# Power.net
KiCad netlist of a schematic drawn in Altium Designer
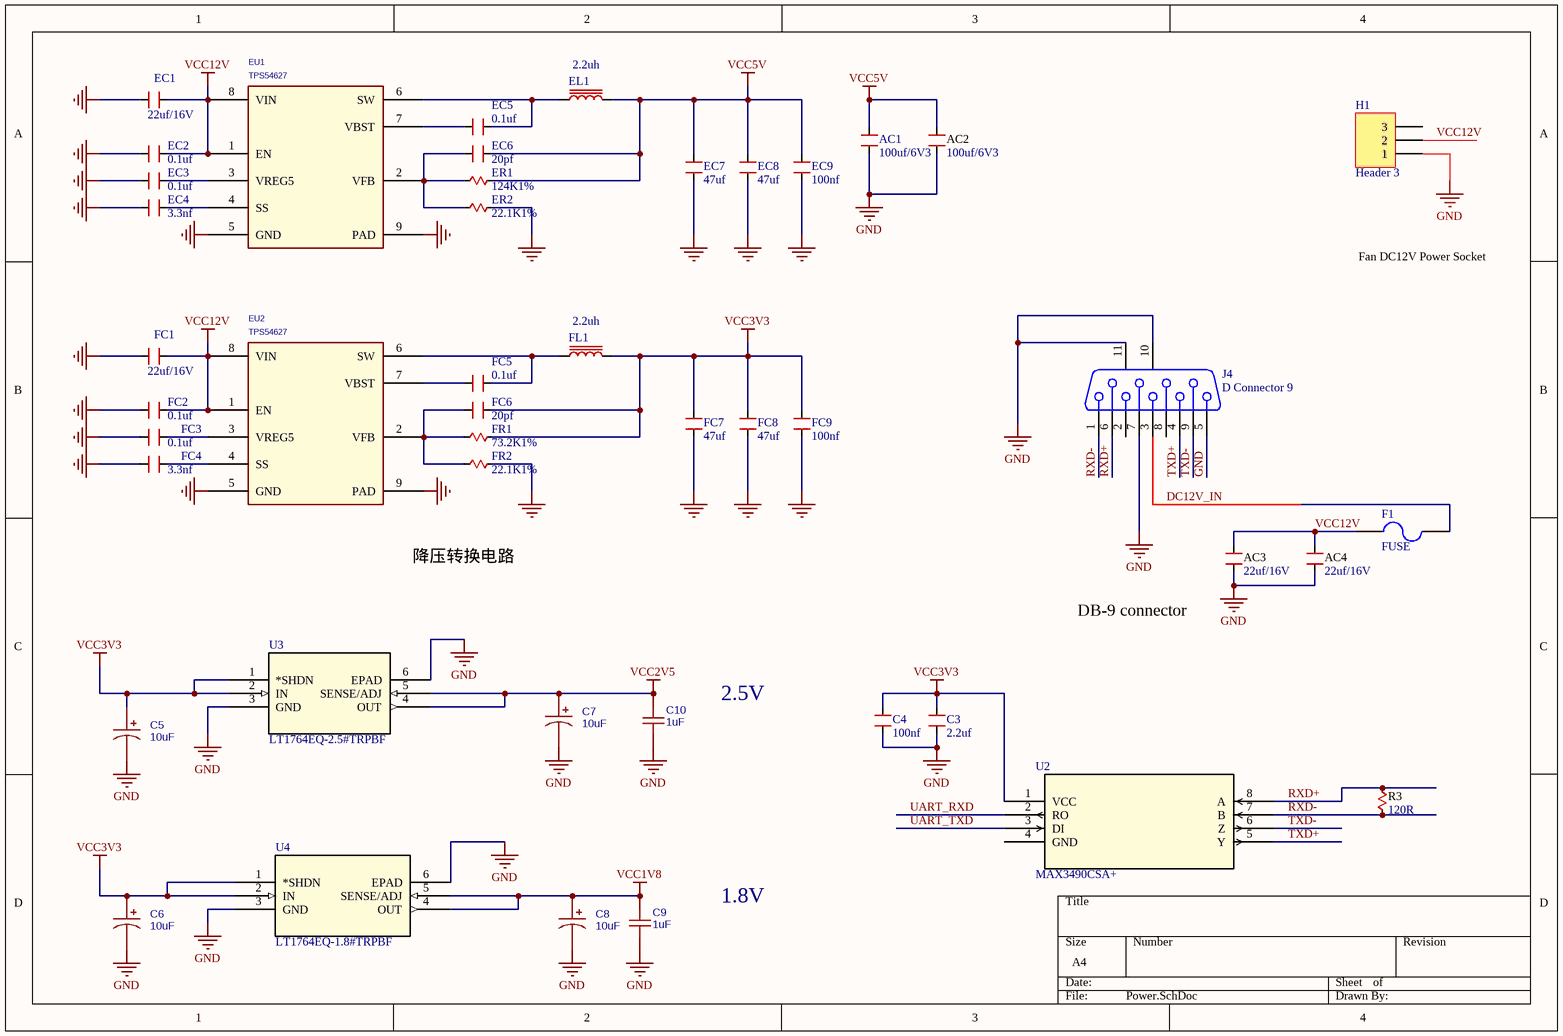
[diagram p0: Power.SchDoc]

(export (version "E")
  (design (tool "Eeschema 10.0.6"))
  (components
    (comp (ref "AC1")
      (value "100uf/6V3")
      (footprint "CAP1206")
      (description "Generic Capacitor")
      (libsource (lib "Miz702fun_20160501") (part "CAPACITOR"))
    )
    (comp (ref "AC2")
      (value "100uf/6V3")
      (footprint "CAP1206")
      (description "Generic Capacitor")
      (libsource (lib "MIZ7035_定制") (part "CAPACITOR"))
    )
    (comp (ref "AC3")
      (value "22uf/16V")
      (footprint "CAP1206")
      (description "Generic Capacitor")
      (libsource (lib "MIZ7035_定制") (part "CAPACITOR"))
    )
    (comp (ref "AC4")
      (value "22uf/16V")
      (footprint "CAP1206")
      (description "Generic Capacitor")
      (libsource (lib "MIZ7035_定制") (part "CAPACITOR"))
    )
    (comp (ref "C3")
      (value "2.2uf")
      (footprint "CAP0402")
      (description "Generic Capacitor")
      (libsource (lib "Miz702fun_20160501") (part "CAPACITOR"))
    )
    (comp (ref "C4")
      (value "100nf")
      (footprint "CAP0402")
      (description "Generic Capacitor")
      (libsource (lib "MainNewLib") (part "CAPACITOR_1"))
    )
    (comp (ref "C5")
      (value "10uF")
      (footprint "CASE-A_3216")
      (fields (field (name "CONTRIBUTOR") "LCEDA_Lib"))
      (libsource (lib "Sub-board") (part "150u"))
    )
    (comp (ref "C6")
      (value "10uF")
      (footprint "CASE-A_3216")
      (fields (field (name "CONTRIBUTOR") "LCEDA_Lib"))
      (libsource (lib "Sub-board") (part "150u"))
    )
    (comp (ref "C7")
      (value "10uF")
      (footprint "CASE-A_3216")
      (fields (field (name "CONTRIBUTOR") "LCEDA_Lib"))
      (libsource (lib "Sub-board") (part "150u"))
    )
    (comp (ref "C8")
      (value "10uF")
      (footprint "CASE-A_3216")
      (fields (field (name "CONTRIBUTOR") "LCEDA_Lib"))
      (libsource (lib "Sub-board") (part "150u"))
    )
    (comp (ref "C9")
      (value "1uF")
      (footprint "CAP0402")
      (fields (field (name "CONTRIBUTOR") "LCEDA_Lib"))
      (libsource (lib "Sub-board") (part "1u"))
    )
    (comp (ref "C10")
      (value "1uF")
      (footprint "CAP0402")
      (fields (field (name "CONTRIBUTOR") "LCEDA_Lib"))
      (libsource (lib "Sub-board") (part "1u"))
    )
    (comp (ref "EC1")
      (value "22uf/16V")
      (footprint "CAP1206")
      (description "Generic Capacitor")
      (libsource (lib "Miz702fun_20160501") (part "CAPACITOR"))
    )
    (comp (ref "EC2")
      (value "0.1uf")
      (footprint "CAP0402")
      (description "Generic Capacitor")
      (libsource (lib "Miz702fun_20160501") (part "CAPACITOR"))
    )
    (comp (ref "EC3")
      (value "0.1uf")
      (footprint "CAP0402")
      (description "Generic Capacitor")
      (libsource (lib "Miz702fun_20160501") (part "CAPACITOR"))
    )
    (comp (ref "EC4")
      (value "3.3nf")
      (footprint "CAP0402")
      (description "Generic Capacitor")
      (libsource (lib "Miz702fun_20160501") (part "CAPACITOR"))
    )
    (comp (ref "EC5")
      (value "0.1uf")
      (footprint "CAP0402")
      (description "Generic Capacitor")
      (libsource (lib "Miz702fun_20160501") (part "CAPACITOR"))
    )
    (comp (ref "EC6")
      (value "20pf")
      (footprint "CAP0402")
      (description "Generic Capacitor")
      (libsource (lib "Miz702fun_20160501") (part "CAPACITOR"))
    )
    (comp (ref "EC7")
      (value "47uf")
      (footprint "CAP0603")
      (description "Generic Capacitor")
      (libsource (lib "Miz702fun_20160501") (part "CAPACITOR"))
    )
    (comp (ref "EC8")
      (value "47uf")
      (footprint "CAP0603")
      (description "Generic Capacitor")
      (libsource (lib "Miz702fun_20160501") (part "CAPACITOR"))
    )
    (comp (ref "EC9")
      (value "100nf")
      (footprint "CAP0402")
      (description "Generic Capacitor")
      (libsource (lib "Miz702fun_20160501") (part "CAPACITOR"))
    )
    (comp (ref "EL1")
      (value "2.2uh")
      (footprint "L4X4X2")
      (description "Generic Inductor")
      (libsource (lib "Digilent") (part "Inductor"))
    )
    (comp (ref "ER1")
      (value "124K1%")
      (footprint "CAP0603")
      (description "Generic Resistor")
      (libsource (lib "Digilent") (part "RESISTOR"))
    )
    (comp (ref "ER2")
      (value "22.1K1%")
      (footprint "CAP0603")
      (description "Generic Resistor")
      (libsource (lib "Digilent") (part "RESISTOR"))
    )
    (comp (ref "EU1")
      (value "TPS54627")
      (footprint "SOP8_EP_127P4X5X1_5")
      (libsource (lib "MainNewLib") (part "TPS54327"))
    )
    (comp (ref "EU2")
      (value "TPS54627")
      (footprint "SOP8_EP_127P4X5X1_5")
      (libsource (lib "MainNewLib") (part "TPS54327"))
    )
    (comp (ref "F1")
      (value "FUSE")
      (footprint "1206")
      (description "Fuse")
      (fields (field (name "PUBLISHER") "Altium Limited"))
      (libsource (lib "jinrylib") (part "Fuse 2"))
    )
    (comp (ref "FC1")
      (value "22uf/16V")
      (footprint "CAP1206")
      (description "Generic Capacitor")
      (libsource (lib "Miz702fun_20160501") (part "CAPACITOR"))
    )
    (comp (ref "FC2")
      (value "0.1uf")
      (footprint "CAP0402")
      (description "Generic Capacitor")
      (libsource (lib "Miz702fun_20160501") (part "CAPACITOR"))
    )
    (comp (ref "FC3")
      (value "0.1uf")
      (footprint "CAP0402")
      (description "Generic Capacitor")
      (libsource (lib "Miz702fun_20160501") (part "CAPACITOR"))
    )
    (comp (ref "FC4")
      (value "3.3nf")
      (footprint "CAP0402")
      (description "Generic Capacitor")
      (libsource (lib "Miz702fun_20160501") (part "CAPACITOR"))
    )
    (comp (ref "FC5")
      (value "0.1uf")
      (footprint "CAP0402")
      (description "Generic Capacitor")
      (libsource (lib "Miz702fun_20160501") (part "CAPACITOR"))
    )
    (comp (ref "FC6")
      (value "20pf")
      (footprint "CAP0402")
      (description "Generic Capacitor")
      (libsource (lib "Miz702fun_20160501") (part "CAPACITOR"))
    )
    (comp (ref "FC7")
      (value "47uf")
      (footprint "CAP0603")
      (description "Generic Capacitor")
      (libsource (lib "Miz702fun_20160501") (part "CAPACITOR"))
    )
    (comp (ref "FC8")
      (value "47uf")
      (footprint "CAP0603")
      (description "Generic Capacitor")
      (libsource (lib "Miz702fun_20160501") (part "CAPACITOR"))
    )
    (comp (ref "FC9")
      (value "100nf")
      (footprint "CAP0402")
      (description "Generic Capacitor")
      (libsource (lib "Miz702fun_20160501") (part "CAPACITOR"))
    )
    (comp (ref "FL1")
      (value "2.2uh")
      (footprint "L4X4X2")
      (description "Generic Inductor")
      (libsource (lib "Digilent") (part "Inductor"))
    )
    (comp (ref "FR1")
      (value "73.2K1%")
      (footprint "CAP0603")
      (description "Generic Resistor")
      (libsource (lib "Digilent") (part "RESISTOR"))
    )
    (comp (ref "FR2")
      (value "22.1K1%")
      (footprint "CAP0603")
      (description "Generic Resistor")
      (libsource (lib "Digilent") (part "RESISTOR"))
    )
    (comp (ref "H1")
      (value "Header 3")
      (footprint "HDR1X3")
      (description "Header, 3-Pin")
      (fields (field (name "PUBLISHER") "Altium Limited"))
      (libsource (lib "jinrylib") (part "Header 3"))
    )
    (comp (ref "J4")
      (value "D Connector 9")
      (footprint "DSUB1.385-2H9")
      (description "Receptacle Assembly, 9 Position, Right Angle")
      (fields (field (name "PUBLISHER") "Altium Limited"))
      (libsource (lib "Miscellaneous Connectors") (part "D Connector 9"))
    )
    (comp (ref "R3")
      (value "120R")
      (footprint "RES0402")
      (description "Generic Resistor")
      (libsource (lib "MainNewLib") (part "RESISTOR"))
    )
    (comp (ref "U2")
      (value "MAX3490CSA+")
      (footprint "21-0041B_8_MXM")
      (description "No Description Available")
      (fields (field (name "COPYRIGHT") "Copyright (C) 2018 Accelerated Designs. All rights reserved"))
      (libsource (lib "MainNewLib") (part "MAX3490CSA+"))
    )
    (comp (ref "U3")
      (value "LT1764EQ-2.5#TRPBF")
      (footprint "DDPAK-5_Q")
      (description "No Description Available")
      (fields
        (field (name "MANUFACTURER_PART_NUMBER") "lt1764eq-2.5#trpbf")
        (field (name "COPYRIGHT") "Copyright (C) 2018 Accelerated Designs. All rights reserved")
      )
      (libsource (lib "MainNewLib") (part "LT1764EQ-2.5#TRPBF"))
    )
    (comp (ref "U4")
      (value "LT1764EQ-1.8#TRPBF")
      (footprint "DDPAK-5_Q")
      (description "No Description Available")
      (fields
        (field (name "MANUFACTURER_PART_NUMBER") "lt1764eq-1.8#trpbf")
        (field (name "COPYRIGHT") "Copyright (C) 2018 Accelerated Designs. All rights reserved")
      )
      (libsource (lib "MainNewLib") (part "LT1764EQ-1.8#TRPBF"))
    )
  )
  (nets
    (net (code "1") (name "/DC12V_IN") (class "Default")
      (node (ref "F1") (pin "2") (pinfunction "2_2") (pintype "passive"))
      (node (ref "J4") (pin "3") (pinfunction "3_3") (pintype "passive"))
    )
    (net (code "2") (name "/RXD+") (class "Default")
      (node (ref "J4") (pin "6") (pinfunction "6_6") (pintype "passive"))
      (node (ref "R3") (pin "1") (pinfunction "1_1") (pintype "passive"))
      (node (ref "U2") (pin "8") (pinfunction "A_8") (pintype "passive"))
    )
    (net (code "3") (name "/RXD-") (class "Default")
      (node (ref "J4") (pin "1") (pinfunction "1_1") (pintype "passive"))
      (node (ref "R3") (pin "2") (pinfunction "2_2") (pintype "passive"))
      (node (ref "U2") (pin "7") (pinfunction "B_7") (pintype "passive"))
    )
    (net (code "4") (name "/TXD+") (class "Default")
      (node (ref "J4") (pin "4") (pinfunction "4_4") (pintype "passive"))
      (node (ref "U2") (pin "5") (pinfunction "Y_5") (pintype "passive"))
    )
    (net (code "5") (name "/TXD-") (class "Default")
      (node (ref "J4") (pin "9") (pinfunction "9_9") (pintype "passive"))
      (node (ref "U2") (pin "6") (pinfunction "Z_6") (pintype "passive"))
    )
    (net (code "6") (name "/UART_RXD") (class "Default")
      (node (ref "U2") (pin "2") (pinfunction "RO_2") (pintype "passive"))
    )
    (net (code "7") (name "/UART_TXD") (class "Default")
      (node (ref "U2") (pin "3") (pinfunction "DI_3") (pintype "passive"))
    )
    (net (code "8") (name "GND") (class "Default")
      (node (ref "AC1") (pin "1") (pinfunction "1_1") (pintype "passive"))
      (node (ref "AC2") (pin "1") (pinfunction "1_1") (pintype "passive"))
      (node (ref "AC3") (pin "1") (pinfunction "1_1") (pintype "passive"))
      (node (ref "AC4") (pin "1") (pinfunction "1_1") (pintype "passive"))
      (node (ref "C10") (pin "1") (pinfunction "1_1") (pintype "passive"))
      (node (ref "C3") (pin "2") (pinfunction "2_2") (pintype "passive"))
      (node (ref "C4") (pin "2") (pinfunction "2_2") (pintype "passive"))
      (node (ref "C5") (pin "2") (pinfunction "2_2") (pintype "passive"))
      (node (ref "C6") (pin "2") (pinfunction "2_2") (pintype "passive"))
      (node (ref "C7") (pin "2") (pinfunction "2_2") (pintype "passive"))
      (node (ref "C8") (pin "2") (pinfunction "2_2") (pintype "passive"))
      (node (ref "C9") (pin "1") (pinfunction "1_1") (pintype "passive"))
      (node (ref "EC1") (pin "1") (pinfunction "1_1") (pintype "passive"))
      (node (ref "EC2") (pin "1") (pinfunction "1_1") (pintype "passive"))
      (node (ref "EC3") (pin "1") (pinfunction "1_1") (pintype "passive"))
      (node (ref "EC4") (pin "1") (pinfunction "1_1") (pintype "passive"))
      (node (ref "EC7") (pin "1") (pinfunction "1_1") (pintype "passive"))
      (node (ref "EC8") (pin "1") (pinfunction "1_1") (pintype "passive"))
      (node (ref "EC9") (pin "1") (pinfunction "1_1") (pintype "passive"))
      (node (ref "ER2") (pin "1") (pinfunction "1_1") (pintype "passive"))
      (node (ref "EU1") (pin "5") (pinfunction "GND_5") (pintype "power_in"))
      (node (ref "EU1") (pin "9") (pinfunction "PAD_9") (pintype "power_in"))
      (node (ref "EU2") (pin "5") (pinfunction "GND_5") (pintype "power_in"))
      (node (ref "EU2") (pin "9") (pinfunction "PAD_9") (pintype "power_in"))
      (node (ref "FC1") (pin "1") (pinfunction "1_1") (pintype "passive"))
      (node (ref "FC2") (pin "1") (pinfunction "1_1") (pintype "passive"))
      (node (ref "FC3") (pin "1") (pinfunction "1_1") (pintype "passive"))
      (node (ref "FC4") (pin "1") (pinfunction "1_1") (pintype "passive"))
      (node (ref "FC7") (pin "1") (pinfunction "1_1") (pintype "passive"))
      (node (ref "FC8") (pin "1") (pinfunction "1_1") (pintype "passive"))
      (node (ref "FC9") (pin "1") (pinfunction "1_1") (pintype "passive"))
      (node (ref "FR2") (pin "1") (pinfunction "1_1") (pintype "passive"))
      (node (ref "H1") (pin "1") (pinfunction "1_1") (pintype "passive"))
      (node (ref "J4") (pin "10") (pinfunction "MH1_10") (pintype "passive"))
      (node (ref "J4") (pin "11") (pinfunction "MH2_11") (pintype "passive"))
      (node (ref "J4") (pin "5") (pinfunction "5_5") (pintype "passive"))
      (node (ref "J4") (pin "7") (pinfunction "7_7") (pintype "passive"))
      (node (ref "U3") (pin "3") (pinfunction "GND_3") (pintype "power_in"))
      (node (ref "U3") (pin "6") (pinfunction "EPAD_6") (pintype "passive"))
      (node (ref "U4") (pin "3") (pinfunction "GND_3") (pintype "power_in"))
      (node (ref "U4") (pin "6") (pinfunction "EPAD_6") (pintype "passive"))
    )
    (net (code "9") (name "Net-(EU1-SS)") (class "Default")
      (node (ref "EC4") (pin "2") (pinfunction "2_2") (pintype "passive"))
      (node (ref "EU1") (pin "4") (pinfunction "SS_4") (pintype "passive"))
    )
    (net (code "10") (name "Net-(EU1-SW)") (class "Default")
      (node (ref "EC5") (pin "2") (pinfunction "2_2") (pintype "passive"))
      (node (ref "EL1") (pin "1") (pinfunction "1_1") (pintype "passive"))
      (node (ref "EU1") (pin "6") (pinfunction "SW_6") (pintype "power_in"))
    )
    (net (code "11") (name "Net-(EU1-VBST)") (class "Default")
      (node (ref "EC5") (pin "1") (pinfunction "1_1") (pintype "passive"))
      (node (ref "EU1") (pin "7") (pinfunction "VBST_7") (pintype "power_in"))
    )
    (net (code "12") (name "Net-(EU1-VFB)") (class "Default")
      (node (ref "EC6") (pin "1") (pinfunction "1_1") (pintype "passive"))
      (node (ref "ER1") (pin "2") (pinfunction "2_2") (pintype "passive"))
      (node (ref "ER2") (pin "2") (pinfunction "2_2") (pintype "passive"))
      (node (ref "EU1") (pin "2") (pinfunction "VFB_2") (pintype "tri_state"))
    )
    (net (code "13") (name "Net-(EU1-VREG5)") (class "Default")
      (node (ref "EC3") (pin "2") (pinfunction "2_2") (pintype "passive"))
      (node (ref "EU1") (pin "3") (pinfunction "VREG5_3") (pintype "power_in"))
    )
    (net (code "14") (name "Net-(EU2-SS)") (class "Default")
      (node (ref "EU2") (pin "4") (pinfunction "SS_4") (pintype "passive"))
      (node (ref "FC4") (pin "2") (pinfunction "2_2") (pintype "passive"))
    )
    (net (code "15") (name "Net-(EU2-SW)") (class "Default")
      (node (ref "EU2") (pin "6") (pinfunction "SW_6") (pintype "power_in"))
      (node (ref "FC5") (pin "2") (pinfunction "2_2") (pintype "passive"))
      (node (ref "FL1") (pin "1") (pinfunction "1_1") (pintype "passive"))
    )
    (net (code "16") (name "Net-(EU2-VBST)") (class "Default")
      (node (ref "EU2") (pin "7") (pinfunction "VBST_7") (pintype "power_in"))
      (node (ref "FC5") (pin "1") (pinfunction "1_1") (pintype "passive"))
    )
    (net (code "17") (name "Net-(EU2-VFB)") (class "Default")
      (node (ref "EU2") (pin "2") (pinfunction "VFB_2") (pintype "tri_state"))
      (node (ref "FC6") (pin "1") (pinfunction "1_1") (pintype "passive"))
      (node (ref "FR1") (pin "2") (pinfunction "2_2") (pintype "passive"))
      (node (ref "FR2") (pin "2") (pinfunction "2_2") (pintype "passive"))
    )
    (net (code "18") (name "Net-(EU2-VREG5)") (class "Default")
      (node (ref "EU2") (pin "3") (pinfunction "VREG5_3") (pintype "power_in"))
      (node (ref "FC3") (pin "2") (pinfunction "2_2") (pintype "passive"))
    )
    (net (code "19") (name "VCC1V8") (class "Default")
      (node (ref "C8") (pin "1") (pinfunction "1_1") (pintype "passive"))
      (node (ref "C9") (pin "2") (pinfunction "2_2") (pintype "passive"))
      (node (ref "U4") (pin "4") (pinfunction "OUT_4") (pintype "output"))
      (node (ref "U4") (pin "5") (pinfunction "SENSE/ADJ_5") (pintype "input"))
    )
    (net (code "20") (name "VCC2V5") (class "Default")
      (node (ref "C10") (pin "2") (pinfunction "2_2") (pintype "passive"))
      (node (ref "C7") (pin "1") (pinfunction "1_1") (pintype "passive"))
      (node (ref "U3") (pin "4") (pinfunction "OUT_4") (pintype "output"))
      (node (ref "U3") (pin "5") (pinfunction "SENSE/ADJ_5") (pintype "input"))
    )
    (net (code "21") (name "VCC3V3") (class "Default")
      (node (ref "C3") (pin "1") (pinfunction "1_1") (pintype "passive"))
      (node (ref "C4") (pin "1") (pinfunction "1_1") (pintype "passive"))
      (node (ref "C5") (pin "1") (pinfunction "1_1") (pintype "passive"))
      (node (ref "C6") (pin "1") (pinfunction "1_1") (pintype "passive"))
      (node (ref "FC6") (pin "2") (pinfunction "2_2") (pintype "passive"))
      (node (ref "FC7") (pin "2") (pinfunction "2_2") (pintype "passive"))
      (node (ref "FC8") (pin "2") (pinfunction "2_2") (pintype "passive"))
      (node (ref "FC9") (pin "2") (pinfunction "2_2") (pintype "passive"))
      (node (ref "FL1") (pin "2") (pinfunction "2_2") (pintype "passive"))
      (node (ref "FR1") (pin "1") (pinfunction "1_1") (pintype "passive"))
      (node (ref "U2") (pin "1") (pinfunction "VCC_1") (pintype "power_in"))
      (node (ref "U3") (pin "1") (pinfunction "*SHDN_1") (pintype "passive"))
      (node (ref "U3") (pin "2") (pinfunction "IN_2") (pintype "input"))
      (node (ref "U4") (pin "1") (pinfunction "*SHDN_1") (pintype "passive"))
      (node (ref "U4") (pin "2") (pinfunction "IN_2") (pintype "input"))
    )
    (net (code "22") (name "VCC5V") (class "Default")
      (node (ref "AC1") (pin "2") (pinfunction "2_2") (pintype "passive"))
      (node (ref "AC2") (pin "2") (pinfunction "2_2") (pintype "passive"))
      (node (ref "EC6") (pin "2") (pinfunction "2_2") (pintype "passive"))
      (node (ref "EC7") (pin "2") (pinfunction "2_2") (pintype "passive"))
      (node (ref "EC8") (pin "2") (pinfunction "2_2") (pintype "passive"))
      (node (ref "EC9") (pin "2") (pinfunction "2_2") (pintype "passive"))
      (node (ref "EL1") (pin "2") (pinfunction "2_2") (pintype "passive"))
      (node (ref "ER1") (pin "1") (pinfunction "1_1") (pintype "passive"))
    )
    (net (code "23") (name "VCC12V") (class "Default")
      (node (ref "AC3") (pin "2") (pinfunction "2_2") (pintype "passive"))
      (node (ref "AC4") (pin "2") (pinfunction "2_2") (pintype "passive"))
      (node (ref "EC1") (pin "2") (pinfunction "2_2") (pintype "passive"))
      (node (ref "EC2") (pin "2") (pinfunction "2_2") (pintype "passive"))
      (node (ref "EU1") (pin "1") (pinfunction "EN_1") (pintype "passive"))
      (node (ref "EU1") (pin "8") (pinfunction "VIN_8") (pintype "power_in"))
      (node (ref "EU2") (pin "1") (pinfunction "EN_1") (pintype "passive"))
      (node (ref "EU2") (pin "8") (pinfunction "VIN_8") (pintype "power_in"))
      (node (ref "F1") (pin "1") (pinfunction "1_1") (pintype "passive"))
      (node (ref "FC1") (pin "2") (pinfunction "2_2") (pintype "passive"))
      (node (ref "FC2") (pin "2") (pinfunction "2_2") (pintype "passive"))
      (node (ref "H1") (pin "2") (pinfunction "2_2") (pintype "passive"))
    )
    (net (code "24") (name "unconnected-(H1-Pad3)") (class "Default")
      (node (ref "H1") (pin "3") (pinfunction "3_3") (pintype "passive"))
    )
    (net (code "25") (name "unconnected-(J4-Pad2)") (class "Default")
      (node (ref "J4") (pin "2") (pinfunction "2_2") (pintype "passive"))
    )
    (net (code "26") (name "unconnected-(J4-Pad8)") (class "Default")
      (node (ref "J4") (pin "8") (pinfunction "8_8") (pintype "passive"))
    )
    (net (code "27") (name "unconnected-(U2-GND-Pad4)") (class "Default")
      (node (ref "U2") (pin "4") (pinfunction "GND_4") (pintype "power_in"))
    )
  )
)
